# 3_Motor.net
KiCad netlist of a schematic drawn in Altium Designer
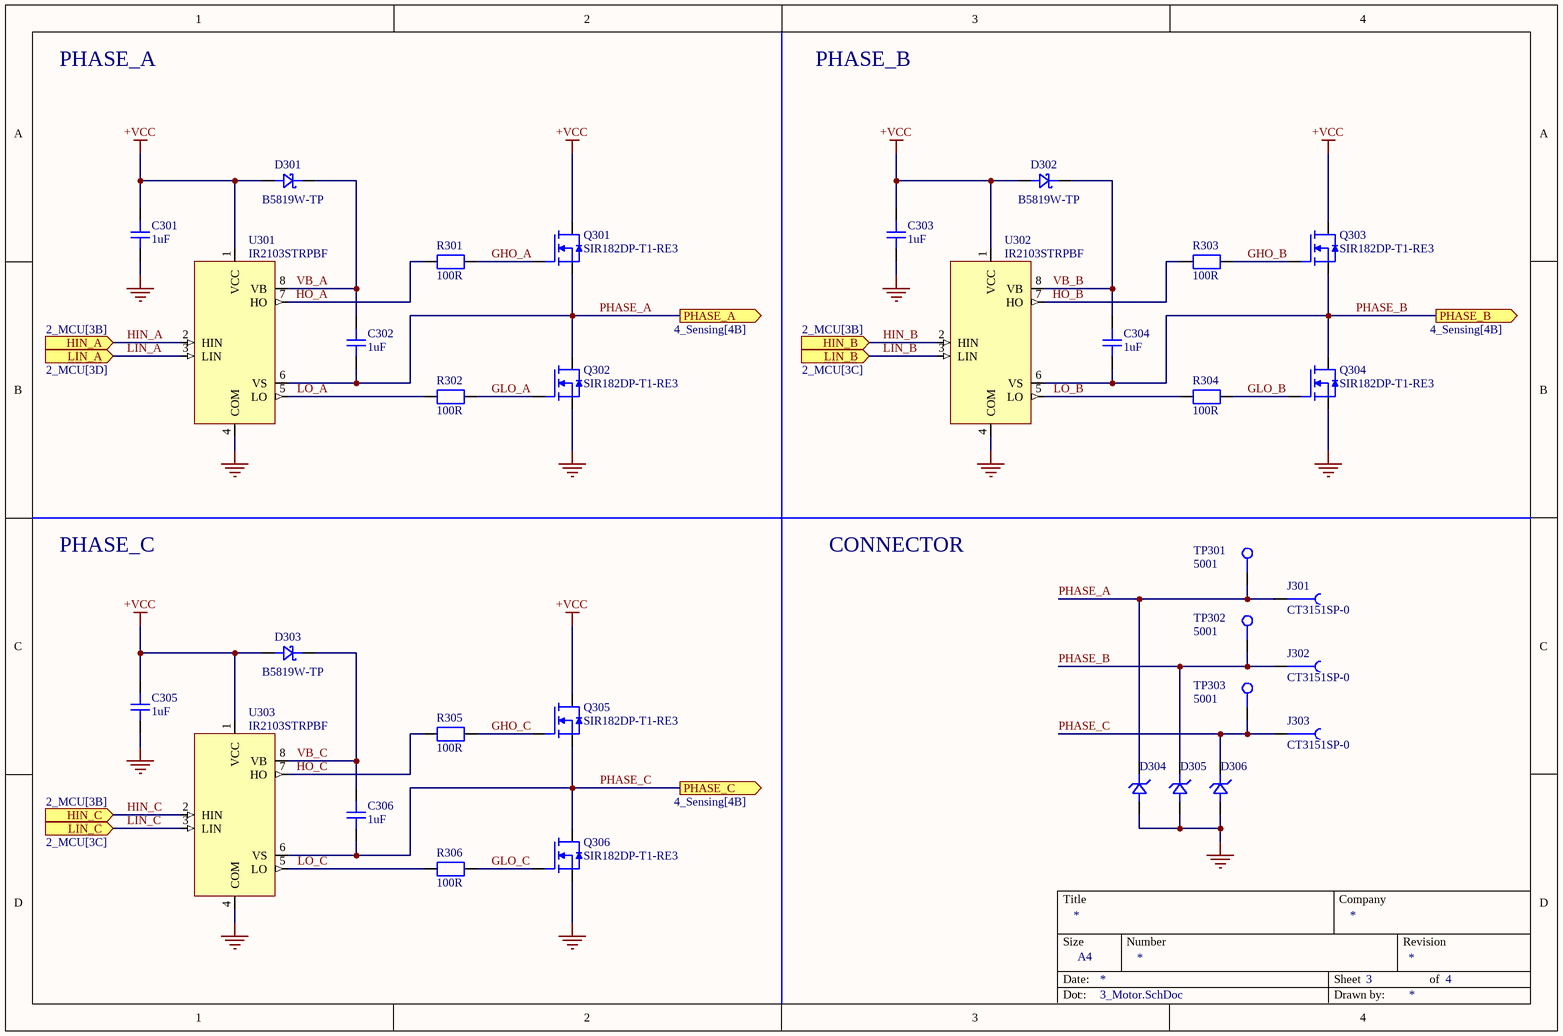
[diagram p0: 3_Motor.SchDoc]

(export (version "E")
  (design (tool "Eeschema 10.0.6"))
  (components
    (comp (ref "C301")
      (value "1uF")
      (footprint "C_Yageo_CC_0603_A")
      (description "Multilayer Ceramic Capacitor, 1 uF, 16 V, ± 10%, X7R, 0603 [1608 Metric]")
      (fields (field (name "TOLERANCE") "10%") (field (name "VOLTAGE") "16V"))
      (libsource (lib "Dennis Micro Computers") (part "C"))
    )
    (comp (ref "C302")
      (value "1uF")
      (footprint "C_Yageo_CC_0603_A")
      (description "Multilayer Ceramic Capacitor, 1 uF, 16 V, ± 10%, X7R, 0603 [1608 Metric]")
      (fields (field (name "TOLERANCE") "10%") (field (name "VOLTAGE") "16V"))
      (libsource (lib "Dennis Micro Computers") (part "C"))
    )
    (comp (ref "C303")
      (value "1uF")
      (footprint "C_Yageo_CC_0603_A")
      (description "Multilayer Ceramic Capacitor, 1 uF, 16 V, ± 10%, X7R, 0603 [1608 Metric]")
      (fields (field (name "TOLERANCE") "10%") (field (name "VOLTAGE") "16V"))
      (libsource (lib "Dennis Micro Computers") (part "C"))
    )
    (comp (ref "C304")
      (value "1uF")
      (footprint "C_Yageo_CC_0603_A")
      (description "Multilayer Ceramic Capacitor, 1 uF, 16 V, ± 10%, X7R, 0603 [1608 Metric]")
      (fields (field (name "TOLERANCE") "10%") (field (name "VOLTAGE") "16V"))
      (libsource (lib "Dennis Micro Computers") (part "C"))
    )
    (comp (ref "C305")
      (value "1uF")
      (footprint "C_Yageo_CC_0603_A")
      (description "Multilayer Ceramic Capacitor, 1 uF, 16 V, ± 10%, X7R, 0603 [1608 Metric]")
      (fields (field (name "TOLERANCE") "10%") (field (name "VOLTAGE") "16V"))
      (libsource (lib "Dennis Micro Computers") (part "C"))
    )
    (comp (ref "C306")
      (value "1uF")
      (footprint "C_Yageo_CC_0603_A")
      (description "Multilayer Ceramic Capacitor, 1 uF, 16 V, ± 10%, X7R, 0603 [1608 Metric]")
      (fields (field (name "TOLERANCE") "10%") (field (name "VOLTAGE") "16V"))
      (libsource (lib "Dennis Micro Computers") (part "C"))
    )
    (comp (ref "D301")
      (value "B5819W-TP")
      (footprint "D_Schottky_MCC_SOD-123")
      (description "Rectifier Diode, Schottky, 1 Phase, 1 Element, 1A, 40V V(RRM), Silicon")
      (libsource (lib "Dennis Micro Computers") (part "D_Schottky"))
    )
    (comp (ref "D302")
      (value "B5819W-TP")
      (footprint "D_Schottky_MCC_SOD-123")
      (description "Rectifier Diode, Schottky, 1 Phase, 1 Element, 1A, 40V V(RRM), Silicon")
      (libsource (lib "Dennis Micro Computers") (part "D_Schottky"))
    )
    (comp (ref "D303")
      (value "B5819W-TP")
      (footprint "D_Schottky_MCC_SOD-123")
      (description "Rectifier Diode, Schottky, 1 Phase, 1 Element, 1A, 40V V(RRM), Silicon")
      (libsource (lib "Dennis Micro Computers") (part "D_Schottky"))
    )
    (comp (ref "D304")
      (value "SMBJ15A-13-F")
      (footprint "D_TVS_Uni_Diodes_DO-214AA_B")
      (description "TVS Diode Single Uni-Dir 15V 600W 2-Pin SMB T/R / TVS DIODE 15VWM 24.4VC SMB")
      (libsource (lib "Dennis Micro Computers") (part "D_TVS_Uni"))
    )
    (comp (ref "D305")
      (value "SMBJ15A-13-F")
      (footprint "D_TVS_Uni_Diodes_DO-214AA_B")
      (description "TVS Diode Single Uni-Dir 15V 600W 2-Pin SMB T/R / TVS DIODE 15VWM 24.4VC SMB")
      (libsource (lib "Dennis Micro Computers") (part "D_TVS_Uni"))
    )
    (comp (ref "D306")
      (value "SMBJ15A-13-F")
      (footprint "D_TVS_Uni_Diodes_DO-214AA_B")
      (description "TVS Diode Single Uni-Dir 15V 600W 2-Pin SMB T/R / TVS DIODE 15VWM 24.4VC SMB")
      (libsource (lib "Dennis Micro Computers") (part "D_TVS_Uni"))
    )
    (comp (ref "J301")
      (value "CT3151SP-0")
      (footprint "J_CalTest_CT3151SP-0")
      (description "Conn 4mm Safety Banana Jack F 1 POS Solder RA Thru-Hole 1 Port Bag")
      (libsource (lib "Dennis Micro Computers") (part "J_01x01_Socket"))
    )
    (comp (ref "J302")
      (value "CT3151SP-0")
      (footprint "J_CalTest_CT3151SP-0")
      (description "Conn 4mm Safety Banana Jack F 1 POS Solder RA Thru-Hole 1 Port Bag")
      (libsource (lib "Dennis Micro Computers") (part "J_01x01_Socket"))
    )
    (comp (ref "J303")
      (value "CT3151SP-0")
      (footprint "J_CalTest_CT3151SP-0")
      (description "Conn 4mm Safety Banana Jack F 1 POS Solder RA Thru-Hole 1 Port Bag")
      (libsource (lib "Dennis Micro Computers") (part "J_01x01_Socket"))
    )
    (comp (ref "Q301")
      (value "SIR182DP-T1-RE3")
      (footprint "Q_Vishay_PowerPACK-SO-8-Single")
      (description "TrenchFET Gen IV Power MOSFET N-Channel Single 60V VDS ±20V VGS 60A ID 8-Pin PowerPAK SOIC T/R")
      (libsource (lib "Dennis Micro Computers") (part "Q_NMOS"))
    )
    (comp (ref "Q302")
      (value "SIR182DP-T1-RE3")
      (footprint "Q_Vishay_PowerPACK-SO-8-Single")
      (description "TrenchFET Gen IV Power MOSFET N-Channel Single 60V VDS ±20V VGS 60A ID 8-Pin PowerPAK SOIC T/R")
      (libsource (lib "Dennis Micro Computers") (part "Q_NMOS"))
    )
    (comp (ref "Q303")
      (value "SIR182DP-T1-RE3")
      (footprint "Q_Vishay_PowerPACK-SO-8-Single")
      (description "TrenchFET Gen IV Power MOSFET N-Channel Single 60V VDS ±20V VGS 60A ID 8-Pin PowerPAK SOIC T/R")
      (libsource (lib "Dennis Micro Computers") (part "Q_NMOS"))
    )
    (comp (ref "Q304")
      (value "SIR182DP-T1-RE3")
      (footprint "Q_Vishay_PowerPACK-SO-8-Single")
      (description "TrenchFET Gen IV Power MOSFET N-Channel Single 60V VDS ±20V VGS 60A ID 8-Pin PowerPAK SOIC T/R")
      (libsource (lib "Dennis Micro Computers") (part "Q_NMOS"))
    )
    (comp (ref "Q305")
      (value "SIR182DP-T1-RE3")
      (footprint "Q_Vishay_PowerPACK-SO-8-Single")
      (description "TrenchFET Gen IV Power MOSFET N-Channel Single 60V VDS ±20V VGS 60A ID 8-Pin PowerPAK SOIC T/R")
      (libsource (lib "Dennis Micro Computers") (part "Q_NMOS"))
    )
    (comp (ref "Q306")
      (value "SIR182DP-T1-RE3")
      (footprint "Q_Vishay_PowerPACK-SO-8-Single")
      (description "TrenchFET Gen IV Power MOSFET N-Channel Single 60V VDS ±20V VGS 60A ID 8-Pin PowerPAK SOIC T/R")
      (libsource (lib "Dennis Micro Computers") (part "Q_NMOS"))
    )
    (comp (ref "R301")
      (value "100R")
      (footprint "R_Yageo_RCL_1206_A")
      (description "SMD Chip Resistor, 100 Ohm, ± 1%, 250 mW, 1206 [3216 Metric], Thick Film, General Purpose")
      (fields (field (name "TOLERANCE") "1%") (field (name "Comment") "RC1206FR-07100RL"))
      (libsource (lib "Dennis Micro Computers") (part "R"))
    )
    (comp (ref "R302")
      (value "100R")
      (footprint "R_Yageo_RCL_1206_A")
      (description "SMD Chip Resistor, 100 Ohm, ± 1%, 250 mW, 1206 [3216 Metric], Thick Film, General Purpose")
      (fields (field (name "TOLERANCE") "1%") (field (name "Comment") "RC1206FR-07100RL"))
      (libsource (lib "Dennis Micro Computers") (part "R"))
    )
    (comp (ref "R303")
      (value "100R")
      (footprint "R_Yageo_RCL_1206_A")
      (description "SMD Chip Resistor, 100 Ohm, ± 1%, 250 mW, 1206 [3216 Metric], Thick Film, General Purpose")
      (fields (field (name "TOLERANCE") "1%") (field (name "Comment") "RC1206FR-07100RL"))
      (libsource (lib "Dennis Micro Computers") (part "R"))
    )
    (comp (ref "R304")
      (value "100R")
      (footprint "R_Yageo_RCL_1206_A")
      (description "SMD Chip Resistor, 100 Ohm, ± 1%, 250 mW, 1206 [3216 Metric], Thick Film, General Purpose")
      (fields (field (name "TOLERANCE") "1%") (field (name "Comment") "RC1206FR-07100RL"))
      (libsource (lib "Dennis Micro Computers") (part "R"))
    )
    (comp (ref "R305")
      (value "100R")
      (footprint "R_Yageo_RCL_1206_A")
      (description "SMD Chip Resistor, 100 Ohm, ± 1%, 250 mW, 1206 [3216 Metric], Thick Film, General Purpose")
      (fields (field (name "TOLERANCE") "1%") (field (name "Comment") "RC1206FR-07100RL"))
      (libsource (lib "Dennis Micro Computers") (part "R"))
    )
    (comp (ref "R306")
      (value "100R")
      (footprint "R_Yageo_RCL_1206_A")
      (description "SMD Chip Resistor, 100 Ohm, ± 1%, 250 mW, 1206 [3216 Metric], Thick Film, General Purpose")
      (fields (field (name "TOLERANCE") "1%") (field (name "Comment") "RC1206FR-07100RL"))
      (libsource (lib "Dennis Micro Computers") (part "R"))
    )
    (comp (ref "TP301")
      (value "5001")
      (footprint "TP_Keystone_TH")
      (libsource (lib "Dennis Micro Computers") (part "TP"))
    )
    (comp (ref "TP302")
      (value "5001")
      (footprint "TP_Keystone_TH")
      (libsource (lib "Dennis Micro Computers") (part "TP"))
    )
    (comp (ref "TP303")
      (value "5001")
      (footprint "TP_Keystone_TH")
      (libsource (lib "Dennis Micro Computers") (part "TP"))
    )
    (comp (ref "U301")
      (value "IR2103STRPBF")
      (footprint "U_Infineon_8-SOIC_3.9mm")
      (description "600 V half-bridge gate driver IC with shoot through protection, SOIC 8N, RoHS")
      (libsource (lib "Dennis Micro Computers") (part "U_IR2103STRPBF"))
    )
    (comp (ref "U302")
      (value "IR2103STRPBF")
      (footprint "U_Infineon_8-SOIC_3.9mm")
      (description "600 V half-bridge gate driver IC with shoot through protection, SOIC 8N, RoHS")
      (libsource (lib "Dennis Micro Computers") (part "U_IR2103STRPBF"))
    )
    (comp (ref "U303")
      (value "IR2103STRPBF")
      (footprint "U_Infineon_8-SOIC_3.9mm")
      (description "600 V half-bridge gate driver IC with shoot through protection, SOIC 8N, RoHS")
      (libsource (lib "Dennis Micro Computers") (part "U_IR2103STRPBF"))
    )
  )
  (nets
    (net (code "1") (name "+VCC") (class "Default")
      (node (ref "C301") (pin "2") (pinfunction "2_2") (pintype "passive"))
      (node (ref "C303") (pin "2") (pinfunction "2_2") (pintype "passive"))
      (node (ref "C305") (pin "2") (pinfunction "2_2") (pintype "passive"))
      (node (ref "D301") (pin "2") (pinfunction "2_2") (pintype "passive"))
      (node (ref "D302") (pin "2") (pinfunction "2_2") (pintype "passive"))
      (node (ref "D303") (pin "2") (pinfunction "2_2") (pintype "passive"))
      (node (ref "Q301") (pin "1") (pinfunction "D_1") (pintype "passive"))
      (node (ref "Q303") (pin "1") (pinfunction "D_1") (pintype "passive"))
      (node (ref "Q305") (pin "1") (pinfunction "D_1") (pintype "passive"))
      (node (ref "U301") (pin "1") (pinfunction "VCC_1") (pintype "power_in"))
      (node (ref "U302") (pin "1") (pinfunction "VCC_1") (pintype "power_in"))
      (node (ref "U303") (pin "1") (pinfunction "VCC_1") (pintype "power_in"))
    )
    (net (code "2") (name "/GHO_A") (class "Default")
      (node (ref "Q301") (pin "2") (pinfunction "G_2") (pintype "passive"))
      (node (ref "R301") (pin "2") (pinfunction "2_2") (pintype "passive"))
    )
    (net (code "3") (name "/GHO_B") (class "Default")
      (node (ref "Q303") (pin "2") (pinfunction "G_2") (pintype "passive"))
      (node (ref "R303") (pin "2") (pinfunction "2_2") (pintype "passive"))
    )
    (net (code "4") (name "/GHO_C") (class "Default")
      (node (ref "Q305") (pin "2") (pinfunction "G_2") (pintype "passive"))
      (node (ref "R305") (pin "2") (pinfunction "2_2") (pintype "passive"))
    )
    (net (code "5") (name "/GLO_A") (class "Default")
      (node (ref "Q302") (pin "2") (pinfunction "G_2") (pintype "passive"))
      (node (ref "R302") (pin "2") (pinfunction "2_2") (pintype "passive"))
    )
    (net (code "6") (name "/GLO_B") (class "Default")
      (node (ref "Q304") (pin "2") (pinfunction "G_2") (pintype "passive"))
      (node (ref "R304") (pin "2") (pinfunction "2_2") (pintype "passive"))
    )
    (net (code "7") (name "/GLO_C") (class "Default")
      (node (ref "Q306") (pin "2") (pinfunction "G_2") (pintype "passive"))
      (node (ref "R306") (pin "2") (pinfunction "2_2") (pintype "passive"))
    )
    (net (code "8") (name "/HIN_A") (class "Default")
      (node (ref "U301") (pin "2") (pinfunction "HIN_2") (pintype "input"))
    )
    (net (code "9") (name "/HIN_B") (class "Default")
      (node (ref "U302") (pin "2") (pinfunction "HIN_2") (pintype "input"))
    )
    (net (code "10") (name "/HIN_C") (class "Default")
      (node (ref "U303") (pin "2") (pinfunction "HIN_2") (pintype "input"))
    )
    (net (code "11") (name "/HO_A") (class "Default")
      (node (ref "R301") (pin "1") (pinfunction "1_1") (pintype "passive"))
      (node (ref "U301") (pin "7") (pinfunction "HO_7") (pintype "output"))
    )
    (net (code "12") (name "/HO_B") (class "Default")
      (node (ref "R303") (pin "1") (pinfunction "1_1") (pintype "passive"))
      (node (ref "U302") (pin "7") (pinfunction "HO_7") (pintype "output"))
    )
    (net (code "13") (name "/HO_C") (class "Default")
      (node (ref "R305") (pin "1") (pinfunction "1_1") (pintype "passive"))
      (node (ref "U303") (pin "7") (pinfunction "HO_7") (pintype "output"))
    )
    (net (code "14") (name "/LIN_A") (class "Default")
      (node (ref "U301") (pin "3") (pinfunction "LIN_3") (pintype "input"))
    )
    (net (code "15") (name "/LIN_B") (class "Default")
      (node (ref "U302") (pin "3") (pinfunction "LIN_3") (pintype "input"))
    )
    (net (code "16") (name "/LIN_C") (class "Default")
      (node (ref "U303") (pin "3") (pinfunction "LIN_3") (pintype "input"))
    )
    (net (code "17") (name "/LO_A") (class "Default")
      (node (ref "R302") (pin "1") (pinfunction "1_1") (pintype "passive"))
      (node (ref "U301") (pin "5") (pinfunction "LO_5") (pintype "output"))
    )
    (net (code "18") (name "/LO_B") (class "Default")
      (node (ref "R304") (pin "1") (pinfunction "1_1") (pintype "passive"))
      (node (ref "U302") (pin "5") (pinfunction "LO_5") (pintype "output"))
    )
    (net (code "19") (name "/LO_C") (class "Default")
      (node (ref "R306") (pin "1") (pinfunction "1_1") (pintype "passive"))
      (node (ref "U303") (pin "5") (pinfunction "LO_5") (pintype "output"))
    )
    (net (code "20") (name "/PHASE_A") (class "Default")
      (node (ref "C302") (pin "1") (pinfunction "1_1") (pintype "passive"))
      (node (ref "D304") (pin "1") (pinfunction "1_1") (pintype "passive"))
      (node (ref "J301") (pin "1") (pinfunction "1_1") (pintype "passive"))
      (node (ref "Q301") (pin "3") (pinfunction "S_3") (pintype "passive"))
      (node (ref "Q302") (pin "1") (pinfunction "D_1") (pintype "passive"))
      (node (ref "TP301") (pin "1") (pinfunction "1_1") (pintype "passive"))
      (node (ref "U301") (pin "6") (pinfunction "VS_6") (pintype "passive"))
    )
    (net (code "21") (name "/PHASE_B") (class "Default")
      (node (ref "C304") (pin "1") (pinfunction "1_1") (pintype "passive"))
      (node (ref "D305") (pin "1") (pinfunction "1_1") (pintype "passive"))
      (node (ref "J302") (pin "1") (pinfunction "1_1") (pintype "passive"))
      (node (ref "Q303") (pin "3") (pinfunction "S_3") (pintype "passive"))
      (node (ref "Q304") (pin "1") (pinfunction "D_1") (pintype "passive"))
      (node (ref "TP302") (pin "1") (pinfunction "1_1") (pintype "passive"))
      (node (ref "U302") (pin "6") (pinfunction "VS_6") (pintype "passive"))
    )
    (net (code "22") (name "/PHASE_C") (class "Default")
      (node (ref "C306") (pin "1") (pinfunction "1_1") (pintype "passive"))
      (node (ref "D306") (pin "1") (pinfunction "1_1") (pintype "passive"))
      (node (ref "J303") (pin "1") (pinfunction "1_1") (pintype "passive"))
      (node (ref "Q305") (pin "3") (pinfunction "S_3") (pintype "passive"))
      (node (ref "Q306") (pin "1") (pinfunction "D_1") (pintype "passive"))
      (node (ref "TP303") (pin "1") (pinfunction "1_1") (pintype "passive"))
      (node (ref "U303") (pin "6") (pinfunction "VS_6") (pintype "passive"))
    )
    (net (code "23") (name "/VB_A") (class "Default")
      (node (ref "C302") (pin "2") (pinfunction "2_2") (pintype "passive"))
      (node (ref "D301") (pin "1") (pinfunction "1_1") (pintype "passive"))
      (node (ref "U301") (pin "8") (pinfunction "VB_8") (pintype "passive"))
    )
    (net (code "24") (name "/VB_B") (class "Default")
      (node (ref "C304") (pin "2") (pinfunction "2_2") (pintype "passive"))
      (node (ref "D302") (pin "1") (pinfunction "1_1") (pintype "passive"))
      (node (ref "U302") (pin "8") (pinfunction "VB_8") (pintype "passive"))
    )
    (net (code "25") (name "/VB_C") (class "Default")
      (node (ref "C306") (pin "2") (pinfunction "2_2") (pintype "passive"))
      (node (ref "D303") (pin "1") (pinfunction "1_1") (pintype "passive"))
      (node (ref "U303") (pin "8") (pinfunction "VB_8") (pintype "passive"))
    )
    (net (code "26") (name "GND") (class "Default")
      (node (ref "C301") (pin "1") (pinfunction "1_1") (pintype "passive"))
      (node (ref "C303") (pin "1") (pinfunction "1_1") (pintype "passive"))
      (node (ref "C305") (pin "1") (pinfunction "1_1") (pintype "passive"))
      (node (ref "D304") (pin "2") (pinfunction "2_2") (pintype "passive"))
      (node (ref "D305") (pin "2") (pinfunction "2_2") (pintype "passive"))
      (node (ref "D306") (pin "2") (pinfunction "2_2") (pintype "passive"))
      (node (ref "Q302") (pin "3") (pinfunction "S_3") (pintype "passive"))
      (node (ref "Q304") (pin "3") (pinfunction "S_3") (pintype "passive"))
      (node (ref "Q306") (pin "3") (pinfunction "S_3") (pintype "passive"))
      (node (ref "U301") (pin "4") (pinfunction "COM_4") (pintype "passive"))
      (node (ref "U302") (pin "4") (pinfunction "COM_4") (pintype "passive"))
      (node (ref "U303") (pin "4") (pinfunction "COM_4") (pintype "passive"))
    )
  )
)
